# qPCR_pcb_breakout_TLC5940PWPR.net
KiCad netlist of a schematic drawn in EAGLE
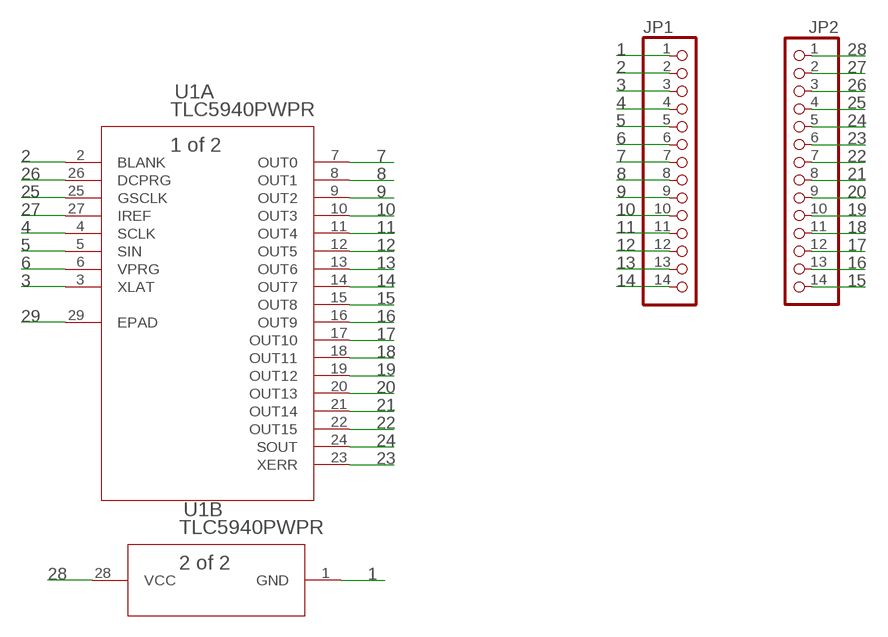
[diagram p0: schematic, sheet 1]

(export (version "E")
  (design (tool "Eeschema 10.0.6"))
  (components
    (comp (ref "JP1")
      (value "PINHD-1X14")
      (footprint "eagle-import:1X14")
      (libsource (lib "eagle-import") (part "PINHD-1X14"))
    )
    (comp (ref "JP2")
      (value "PINHD-1X14")
      (footprint "eagle-import:1X14")
      (libsource (lib "eagle-import") (part "PINHD-1X14"))
    )
    (comp (ref "U1")
      (value "TLC5940PWPR")
      (footprint "eagle-import:PWP28_6P17X2P4")
      (fields (field (name "MANUFACTURER") "Texas Instruments"))
      (libsource (lib "eagle-import") (part "TLC5940PWPR"))
    )
  )
  (nets
    (net (code "1") (name "/1") (class "Default")
      (node (ref "JP1") (pin "1") (pinfunction "1_1") (pintype "passive"))
      (node (ref "U1") (pin "1") (pinfunction "GND_1") (pintype "power_in"))
    )
    (net (code "2") (name "/2") (class "Default")
      (node (ref "JP1") (pin "2") (pinfunction "2_2") (pintype "passive"))
      (node (ref "U1") (pin "2") (pinfunction "BLANK_2") (pintype "input"))
    )
    (net (code "3") (name "/3") (class "Default")
      (node (ref "JP1") (pin "3") (pinfunction "3_3") (pintype "passive"))
      (node (ref "U1") (pin "3") (pinfunction "XLAT_3") (pintype "input"))
    )
    (net (code "4") (name "/4") (class "Default")
      (node (ref "JP1") (pin "4") (pinfunction "4_4") (pintype "passive"))
      (node (ref "U1") (pin "4") (pinfunction "SCLK_4") (pintype "input"))
    )
    (net (code "5") (name "/5") (class "Default")
      (node (ref "JP1") (pin "5") (pinfunction "5_5") (pintype "passive"))
      (node (ref "U1") (pin "5") (pinfunction "SIN_5") (pintype "input"))
    )
    (net (code "6") (name "/6") (class "Default")
      (node (ref "JP1") (pin "6") (pinfunction "6_6") (pintype "passive"))
      (node (ref "U1") (pin "6") (pinfunction "VPRG_6") (pintype "input"))
    )
    (net (code "7") (name "/7") (class "Default")
      (node (ref "JP1") (pin "7") (pinfunction "7_7") (pintype "passive"))
      (node (ref "U1") (pin "7") (pinfunction "OUT0_7") (pintype "output"))
    )
    (net (code "8") (name "/8") (class "Default")
      (node (ref "JP1") (pin "8") (pinfunction "8_8") (pintype "passive"))
      (node (ref "U1") (pin "8") (pinfunction "OUT1_8") (pintype "output"))
    )
    (net (code "9") (name "/9") (class "Default")
      (node (ref "JP1") (pin "9") (pinfunction "9_9") (pintype "passive"))
      (node (ref "U1") (pin "9") (pinfunction "OUT2_9") (pintype "output"))
    )
    (net (code "10") (name "/10") (class "Default")
      (node (ref "JP1") (pin "10") (pinfunction "10_10") (pintype "passive"))
      (node (ref "U1") (pin "10") (pinfunction "OUT3_10") (pintype "output"))
    )
    (net (code "11") (name "/11") (class "Default")
      (node (ref "JP1") (pin "11") (pinfunction "11_11") (pintype "passive"))
      (node (ref "U1") (pin "11") (pinfunction "OUT4_11") (pintype "output"))
    )
    (net (code "12") (name "/12") (class "Default")
      (node (ref "JP1") (pin "12") (pinfunction "12_12") (pintype "passive"))
      (node (ref "U1") (pin "12") (pinfunction "OUT5_12") (pintype "output"))
    )
    (net (code "13") (name "/13") (class "Default")
      (node (ref "JP1") (pin "13") (pinfunction "13_13") (pintype "passive"))
      (node (ref "U1") (pin "13") (pinfunction "OUT6_13") (pintype "output"))
    )
    (net (code "14") (name "/14") (class "Default")
      (node (ref "JP1") (pin "14") (pinfunction "14_14") (pintype "passive"))
      (node (ref "U1") (pin "14") (pinfunction "OUT7_14") (pintype "output"))
    )
    (net (code "15") (name "/15") (class "Default")
      (node (ref "JP2") (pin "14") (pinfunction "14_14") (pintype "passive"))
      (node (ref "U1") (pin "15") (pinfunction "OUT8_15") (pintype "output"))
    )
    (net (code "16") (name "/16") (class "Default")
      (node (ref "JP2") (pin "13") (pinfunction "13_13") (pintype "passive"))
      (node (ref "U1") (pin "16") (pinfunction "OUT9_16") (pintype "output"))
    )
    (net (code "17") (name "/17") (class "Default")
      (node (ref "JP2") (pin "12") (pinfunction "12_12") (pintype "passive"))
      (node (ref "U1") (pin "17") (pinfunction "OUT10_17") (pintype "output"))
    )
    (net (code "18") (name "/18") (class "Default")
      (node (ref "JP2") (pin "11") (pinfunction "11_11") (pintype "passive"))
      (node (ref "U1") (pin "18") (pinfunction "OUT11_18") (pintype "output"))
    )
    (net (code "19") (name "/19") (class "Default")
      (node (ref "JP2") (pin "10") (pinfunction "10_10") (pintype "passive"))
      (node (ref "U1") (pin "19") (pinfunction "OUT12_19") (pintype "output"))
    )
    (net (code "20") (name "/20") (class "Default")
      (node (ref "JP2") (pin "9") (pinfunction "9_9") (pintype "passive"))
      (node (ref "U1") (pin "20") (pinfunction "OUT13_20") (pintype "output"))
    )
    (net (code "21") (name "/21") (class "Default")
      (node (ref "JP2") (pin "8") (pinfunction "8_8") (pintype "passive"))
      (node (ref "U1") (pin "21") (pinfunction "OUT14_21") (pintype "output"))
    )
    (net (code "22") (name "/22") (class "Default")
      (node (ref "JP2") (pin "7") (pinfunction "7_7") (pintype "passive"))
      (node (ref "U1") (pin "22") (pinfunction "OUT15_22") (pintype "output"))
    )
    (net (code "23") (name "/23") (class "Default")
      (node (ref "JP2") (pin "6") (pinfunction "6_6") (pintype "passive"))
      (node (ref "U1") (pin "23") (pinfunction "XERR_23") (pintype "output"))
    )
    (net (code "24") (name "/24") (class "Default")
      (node (ref "JP2") (pin "5") (pinfunction "5_5") (pintype "passive"))
      (node (ref "U1") (pin "24") (pinfunction "SOUT_24") (pintype "output"))
    )
    (net (code "25") (name "/25") (class "Default")
      (node (ref "JP2") (pin "4") (pinfunction "4_4") (pintype "passive"))
      (node (ref "U1") (pin "25") (pinfunction "GSCLK_25") (pintype "input"))
    )
    (net (code "26") (name "/26") (class "Default")
      (node (ref "JP2") (pin "3") (pinfunction "3_3") (pintype "passive"))
      (node (ref "U1") (pin "26") (pinfunction "DCPRG_26") (pintype "input"))
    )
    (net (code "27") (name "/27") (class "Default")
      (node (ref "JP2") (pin "2") (pinfunction "2_2") (pintype "passive"))
      (node (ref "U1") (pin "27") (pinfunction "IREF_27") (pintype "input"))
    )
    (net (code "28") (name "/28") (class "Default")
      (node (ref "JP2") (pin "1") (pinfunction "1_1") (pintype "passive"))
      (node (ref "U1") (pin "28") (pinfunction "VCC_28") (pintype "power_in"))
    )
    (net (code "29") (name "/29") (class "Default")
      (node (ref "U1") (pin "29") (pinfunction "EPAD_29") (pintype "passive"))
    )
  )
)
